# BCC_1_1.net
KiCad netlist of a schematic drawn in EAGLE
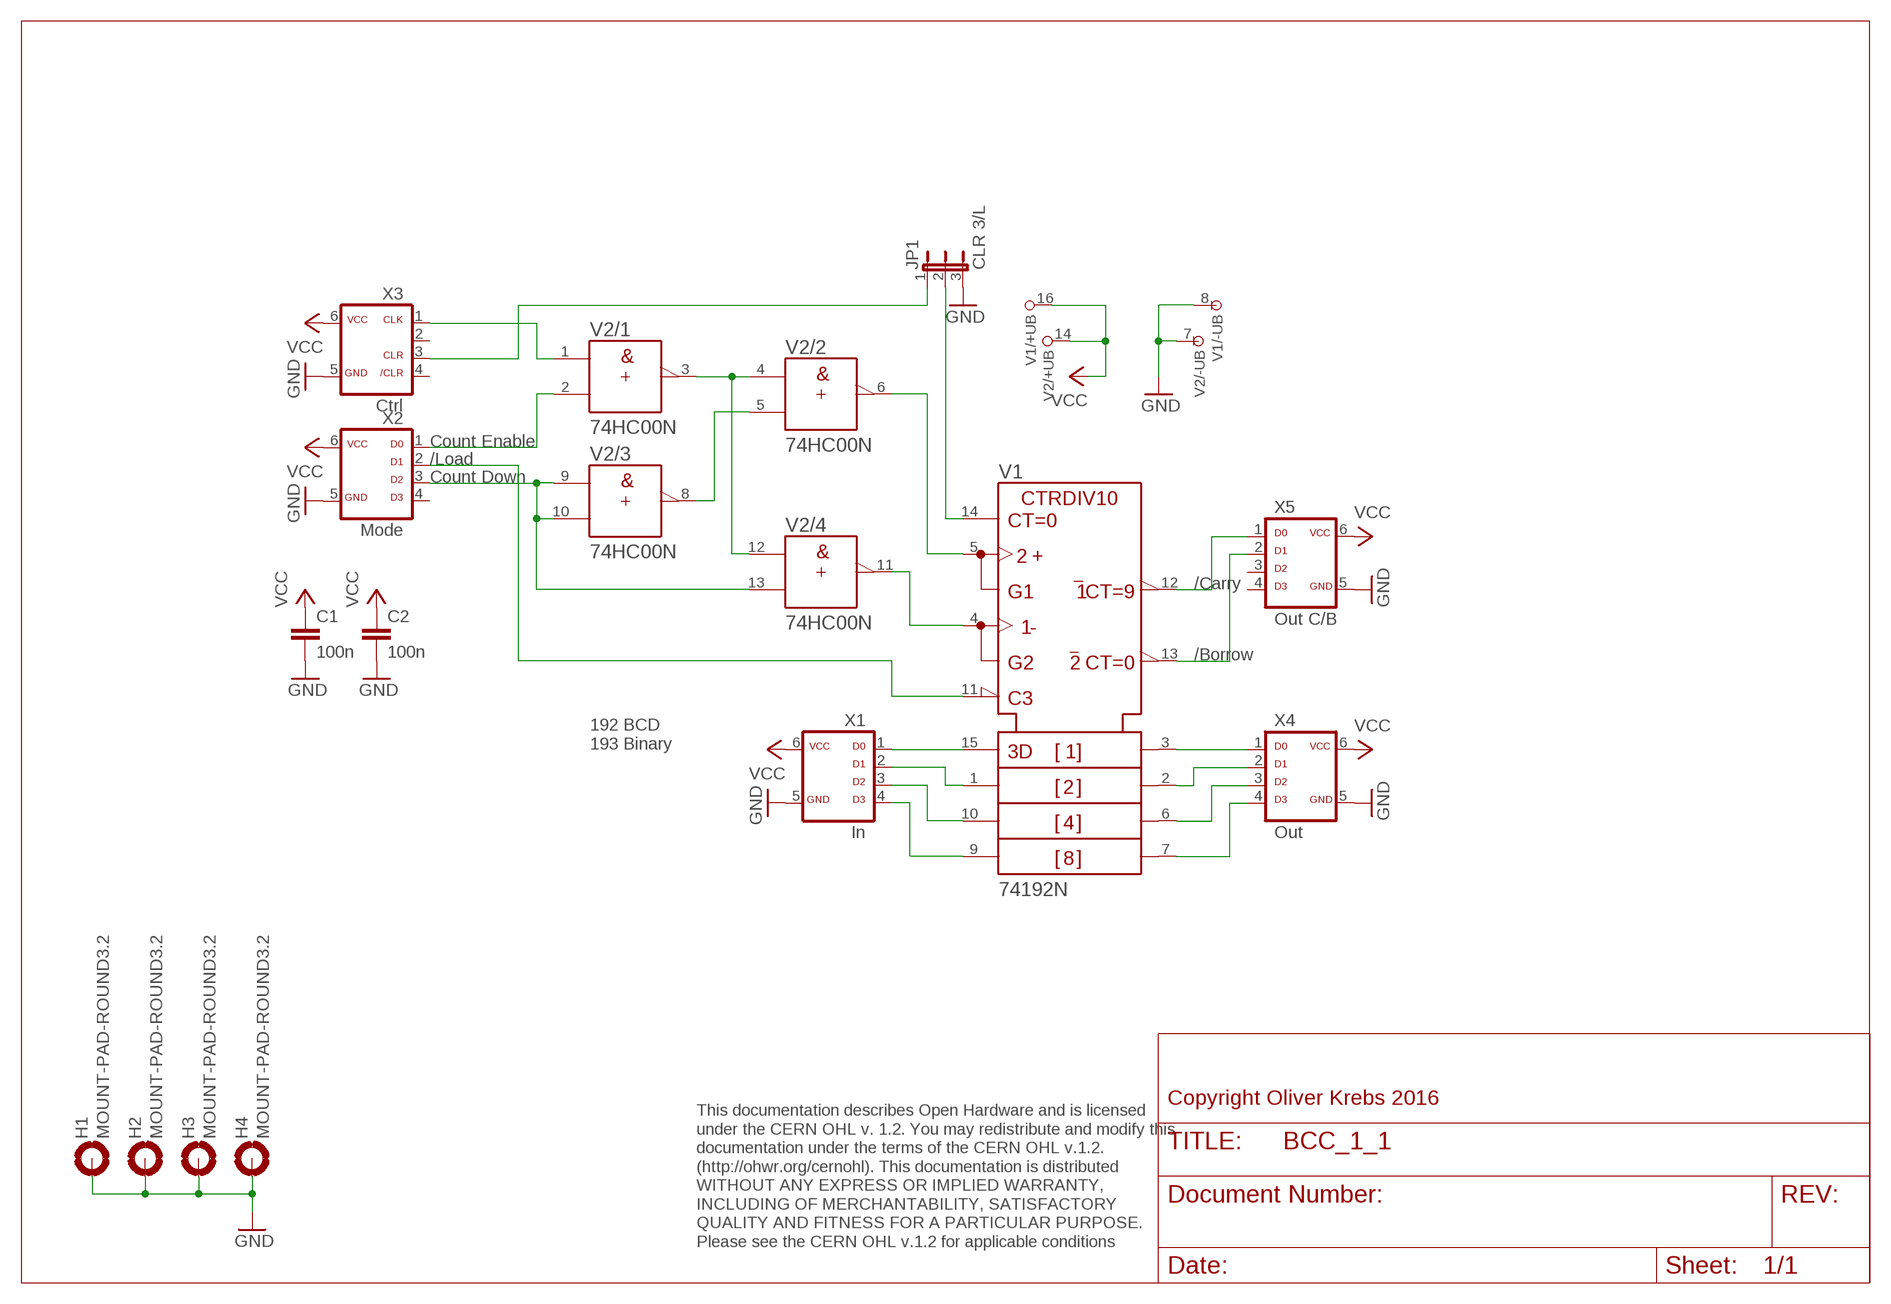
[diagram p0: schematic, sheet 1]

(export (version "E")
  (design (tool "Eeschema 10.0.6"))
  (components
    (comp (ref "C1")
      (value "100n")
      (footprint "eagle-import:C050-025X075")
      (libsource (lib "eagle-import") (part "C-EU050-025X075"))
    )
    (comp (ref "C2")
      (value "100n")
      (footprint "eagle-import:C050-025X075")
      (libsource (lib "eagle-import") (part "C-EU050-025X075"))
    )
    (comp (ref "H1")
      (value "MOUNT-PAD-ROUND3.2")
      (footprint "eagle-import:3,2-PAD")
      (libsource (lib "eagle-import") (part "MOUNT-PAD-ROUND3.2"))
    )
    (comp (ref "H2")
      (value "MOUNT-PAD-ROUND3.2")
      (footprint "eagle-import:3,2-PAD")
      (libsource (lib "eagle-import") (part "MOUNT-PAD-ROUND3.2"))
    )
    (comp (ref "H3")
      (value "MOUNT-PAD-ROUND3.2")
      (footprint "eagle-import:3,2-PAD")
      (libsource (lib "eagle-import") (part "MOUNT-PAD-ROUND3.2"))
    )
    (comp (ref "H4")
      (value "MOUNT-PAD-ROUND3.2")
      (footprint "eagle-import:3,2-PAD")
      (libsource (lib "eagle-import") (part "MOUNT-PAD-ROUND3.2"))
    )
    (comp (ref "JP1")
      (value "CLR 3/L")
      (footprint "eagle-import:JP2")
      (libsource (lib "eagle-import") (part "JP2E"))
    )
    (comp (ref "V1")
      (value "74192N")
      (footprint "eagle-import:DIL16")
      (libsource (lib "eagle-import") (part "74192N"))
    )
    (comp (ref "V2")
      (value "74HC00N")
      (footprint "eagle-import:DIL14")
      (libsource (lib "eagle-import") (part "7400NHC"))
    )
    (comp (ref "X1")
      (value "In")
      (footprint "eagle-import:ML-6")
      (libsource (lib "eagle-import") (part "ML6D"))
    )
    (comp (ref "X2")
      (value "Mode")
      (footprint "eagle-import:ML-6")
      (libsource (lib "eagle-import") (part "ML6D"))
    )
    (comp (ref "X3")
      (value "Ctrl")
      (footprint "eagle-import:ML-6")
      (libsource (lib "eagle-import") (part "ML6C"))
    )
    (comp (ref "X4")
      (value "Out")
      (footprint "eagle-import:ML-6")
      (libsource (lib "eagle-import") (part "ML6D"))
    )
    (comp (ref "X5")
      (value "Out C/B")
      (footprint "eagle-import:ML-6")
      (libsource (lib "eagle-import") (part "ML6D"))
    )
  )
  (nets
    (net (code "1") (name "GND") (class "Default")
      (node (ref "C1") (pin "2") (pinfunction "2_2") (pintype "passive"))
      (node (ref "C2") (pin "2") (pinfunction "2_2") (pintype "passive"))
      (node (ref "H1") (pin "B3,2") (pinfunction "MOUNT_B3,2") (pintype "passive"))
      (node (ref "H2") (pin "B3,2") (pinfunction "MOUNT_B3,2") (pintype "passive"))
      (node (ref "H3") (pin "B3,2") (pinfunction "MOUNT_B3,2") (pintype "passive"))
      (node (ref "H4") (pin "B3,2") (pinfunction "MOUNT_B3,2") (pintype "passive"))
      (node (ref "JP1") (pin "3") (pinfunction "3_3") (pintype "passive"))
      (node (ref "V1") (pin "8") (pinfunction "-UB_8") (pintype "power_in"))
      (node (ref "V2") (pin "7") (pinfunction "-UB_7") (pintype "power_in"))
      (node (ref "X1") (pin "5") (pinfunction "5_5") (pintype "passive"))
      (node (ref "X2") (pin "5") (pinfunction "5_5") (pintype "passive"))
      (node (ref "X3") (pin "5") (pinfunction "5_5") (pintype "passive"))
      (node (ref "X4") (pin "5") (pinfunction "5_5") (pintype "passive"))
      (node (ref "X5") (pin "5") (pinfunction "5_5") (pintype "passive"))
    )
    (net (code "2") (name "Net-(JP1-Pad1)") (class "Default")
      (node (ref "JP1") (pin "1") (pinfunction "1_1") (pintype "passive"))
      (node (ref "X3") (pin "3") (pinfunction "3_3") (pintype "passive"))
    )
    (net (code "3") (name "Net-(V1C-A)") (class "Default")
      (node (ref "V1") (pin "15") (pinfunction "A_15") (pintype "input"))
      (node (ref "X1") (pin "1") (pinfunction "1_1") (pintype "passive"))
    )
    (net (code "4") (name "Net-(V1C-B)") (class "Default")
      (node (ref "V1") (pin "1") (pinfunction "B_1") (pintype "input"))
      (node (ref "X1") (pin "2") (pinfunction "2_2") (pintype "passive"))
    )
    (net (code "5") (name "Net-(V1C-C)") (class "Default")
      (node (ref "V1") (pin "10") (pinfunction "C_10") (pintype "input"))
      (node (ref "X1") (pin "3") (pinfunction "3_3") (pintype "passive"))
    )
    (net (code "6") (name "Net-(V1C-CLR)") (class "Default")
      (node (ref "JP1") (pin "2") (pinfunction "2_2") (pintype "passive"))
      (node (ref "V1") (pin "14") (pinfunction "CLR_14") (pintype "input"))
    )
    (net (code "7") (name "Net-(V1C-D)") (class "Default")
      (node (ref "V1") (pin "9") (pinfunction "D_9") (pintype "input"))
      (node (ref "X1") (pin "4") (pinfunction "4_4") (pintype "passive"))
    )
    (net (code "8") (name "Net-(V1C-DOWN)") (class "Default")
      (node (ref "V1") (pin "4") (pinfunction "DOWN_4") (pintype "input"))
      (node (ref "V2") (pin "11") (pinfunction "Y_11") (pintype "output"))
    )
    (net (code "9") (name "Net-(V1C-QA)") (class "Default")
      (node (ref "V1") (pin "3") (pinfunction "QA_3") (pintype "output"))
      (node (ref "X4") (pin "1") (pinfunction "1_1") (pintype "passive"))
    )
    (net (code "10") (name "Net-(V1C-QB)") (class "Default")
      (node (ref "V1") (pin "2") (pinfunction "QB_2") (pintype "output"))
      (node (ref "X4") (pin "2") (pinfunction "2_2") (pintype "passive"))
    )
    (net (code "11") (name "Net-(V1C-QC)") (class "Default")
      (node (ref "V1") (pin "6") (pinfunction "QC_6") (pintype "output"))
      (node (ref "X4") (pin "3") (pinfunction "3_3") (pintype "passive"))
    )
    (net (code "12") (name "Net-(V1C-QD)") (class "Default")
      (node (ref "V1") (pin "7") (pinfunction "QD_7") (pintype "output"))
      (node (ref "X4") (pin "4") (pinfunction "4_4") (pintype "passive"))
    )
    (net (code "13") (name "Net-(V1C-UP)") (class "Default")
      (node (ref "V1") (pin "5") (pinfunction "UP_5") (pintype "input"))
      (node (ref "V2") (pin "6") (pinfunction "Y_6") (pintype "output"))
    )
    (net (code "14") (name "Net-(V1C-~{BO})") (class "Default")
      (node (ref "V1") (pin "13") (pinfunction "~{BO}_13") (pintype "output"))
      (node (ref "X5") (pin "2") (pinfunction "2_2") (pintype "passive"))
    )
    (net (code "15") (name "Net-(V1C-~{CO})") (class "Default")
      (node (ref "V1") (pin "12") (pinfunction "~{CO}_12") (pintype "output"))
      (node (ref "X5") (pin "1") (pinfunction "1_1") (pintype "passive"))
    )
    (net (code "16") (name "Net-(V1C-~{LOAD})") (class "Default")
      (node (ref "V1") (pin "11") (pinfunction "~{LOAD}_11") (pintype "input"))
      (node (ref "X2") (pin "2") (pinfunction "2_2") (pintype "passive"))
    )
    (net (code "17") (name "Net-(V2C-A)") (class "Default")
      (node (ref "V2") (pin "1") (pinfunction "A_1") (pintype "input"))
      (node (ref "X3") (pin "1") (pinfunction "1_1") (pintype "passive"))
    )
    (net (code "18") (name "Net-(V2C-B)") (class "Default")
      (node (ref "V2") (pin "2") (pinfunction "B_2") (pintype "input"))
      (node (ref "X2") (pin "1") (pinfunction "1_1") (pintype "passive"))
    )
    (net (code "19") (name "Net-(V2C-Y)") (class "Default")
      (node (ref "V2") (pin "12") (pinfunction "A_12") (pintype "input"))
      (node (ref "V2") (pin "3") (pinfunction "Y_3") (pintype "output"))
      (node (ref "V2") (pin "4") (pinfunction "A_4") (pintype "input"))
    )
    (net (code "20") (name "Net-(V2D-B)") (class "Default")
      (node (ref "V2") (pin "5") (pinfunction "B_5") (pintype "input"))
      (node (ref "V2") (pin "8") (pinfunction "Y_8") (pintype "output"))
    )
    (net (code "21") (name "Net-(V2E-A)") (class "Default")
      (node (ref "V2") (pin "10") (pinfunction "B_10") (pintype "input"))
      (node (ref "V2") (pin "13") (pinfunction "B_13") (pintype "input"))
      (node (ref "V2") (pin "9") (pinfunction "A_9") (pintype "input"))
      (node (ref "X2") (pin "3") (pinfunction "3_3") (pintype "passive"))
    )
    (net (code "22") (name "VCC") (class "Default")
      (node (ref "C1") (pin "1") (pinfunction "1_1") (pintype "passive"))
      (node (ref "C2") (pin "1") (pinfunction "1_1") (pintype "passive"))
      (node (ref "V1") (pin "16") (pinfunction "+UB_16") (pintype "power_in"))
      (node (ref "V2") (pin "14") (pinfunction "+UB_14") (pintype "power_in"))
      (node (ref "X1") (pin "6") (pinfunction "6_6") (pintype "passive"))
      (node (ref "X2") (pin "6") (pinfunction "6_6") (pintype "passive"))
      (node (ref "X3") (pin "6") (pinfunction "6_6") (pintype "passive"))
      (node (ref "X4") (pin "6") (pinfunction "6_6") (pintype "passive"))
      (node (ref "X5") (pin "6") (pinfunction "6_6") (pintype "passive"))
    )
    (net (code "23") (name "unconnected-(X2-Pad4)") (class "Default")
      (node (ref "X2") (pin "4") (pinfunction "4_4") (pintype "passive"))
    )
    (net (code "24") (name "unconnected-(X3-Pad2)") (class "Default")
      (node (ref "X3") (pin "2") (pinfunction "2_2") (pintype "passive"))
    )
    (net (code "25") (name "unconnected-(X3-Pad4)") (class "Default")
      (node (ref "X3") (pin "4") (pinfunction "4_4") (pintype "passive"))
    )
    (net (code "26") (name "unconnected-(X5-Pad3)") (class "Default")
      (node (ref "X5") (pin "3") (pinfunction "3_3") (pintype "passive"))
    )
    (net (code "27") (name "unconnected-(X5-Pad4)") (class "Default")
      (node (ref "X5") (pin "4") (pinfunction "4_4") (pintype "passive"))
    )
  )
)
